# atari-2600-video-mod-v1_0.net
KiCad netlist of a schematic drawn in EAGLE
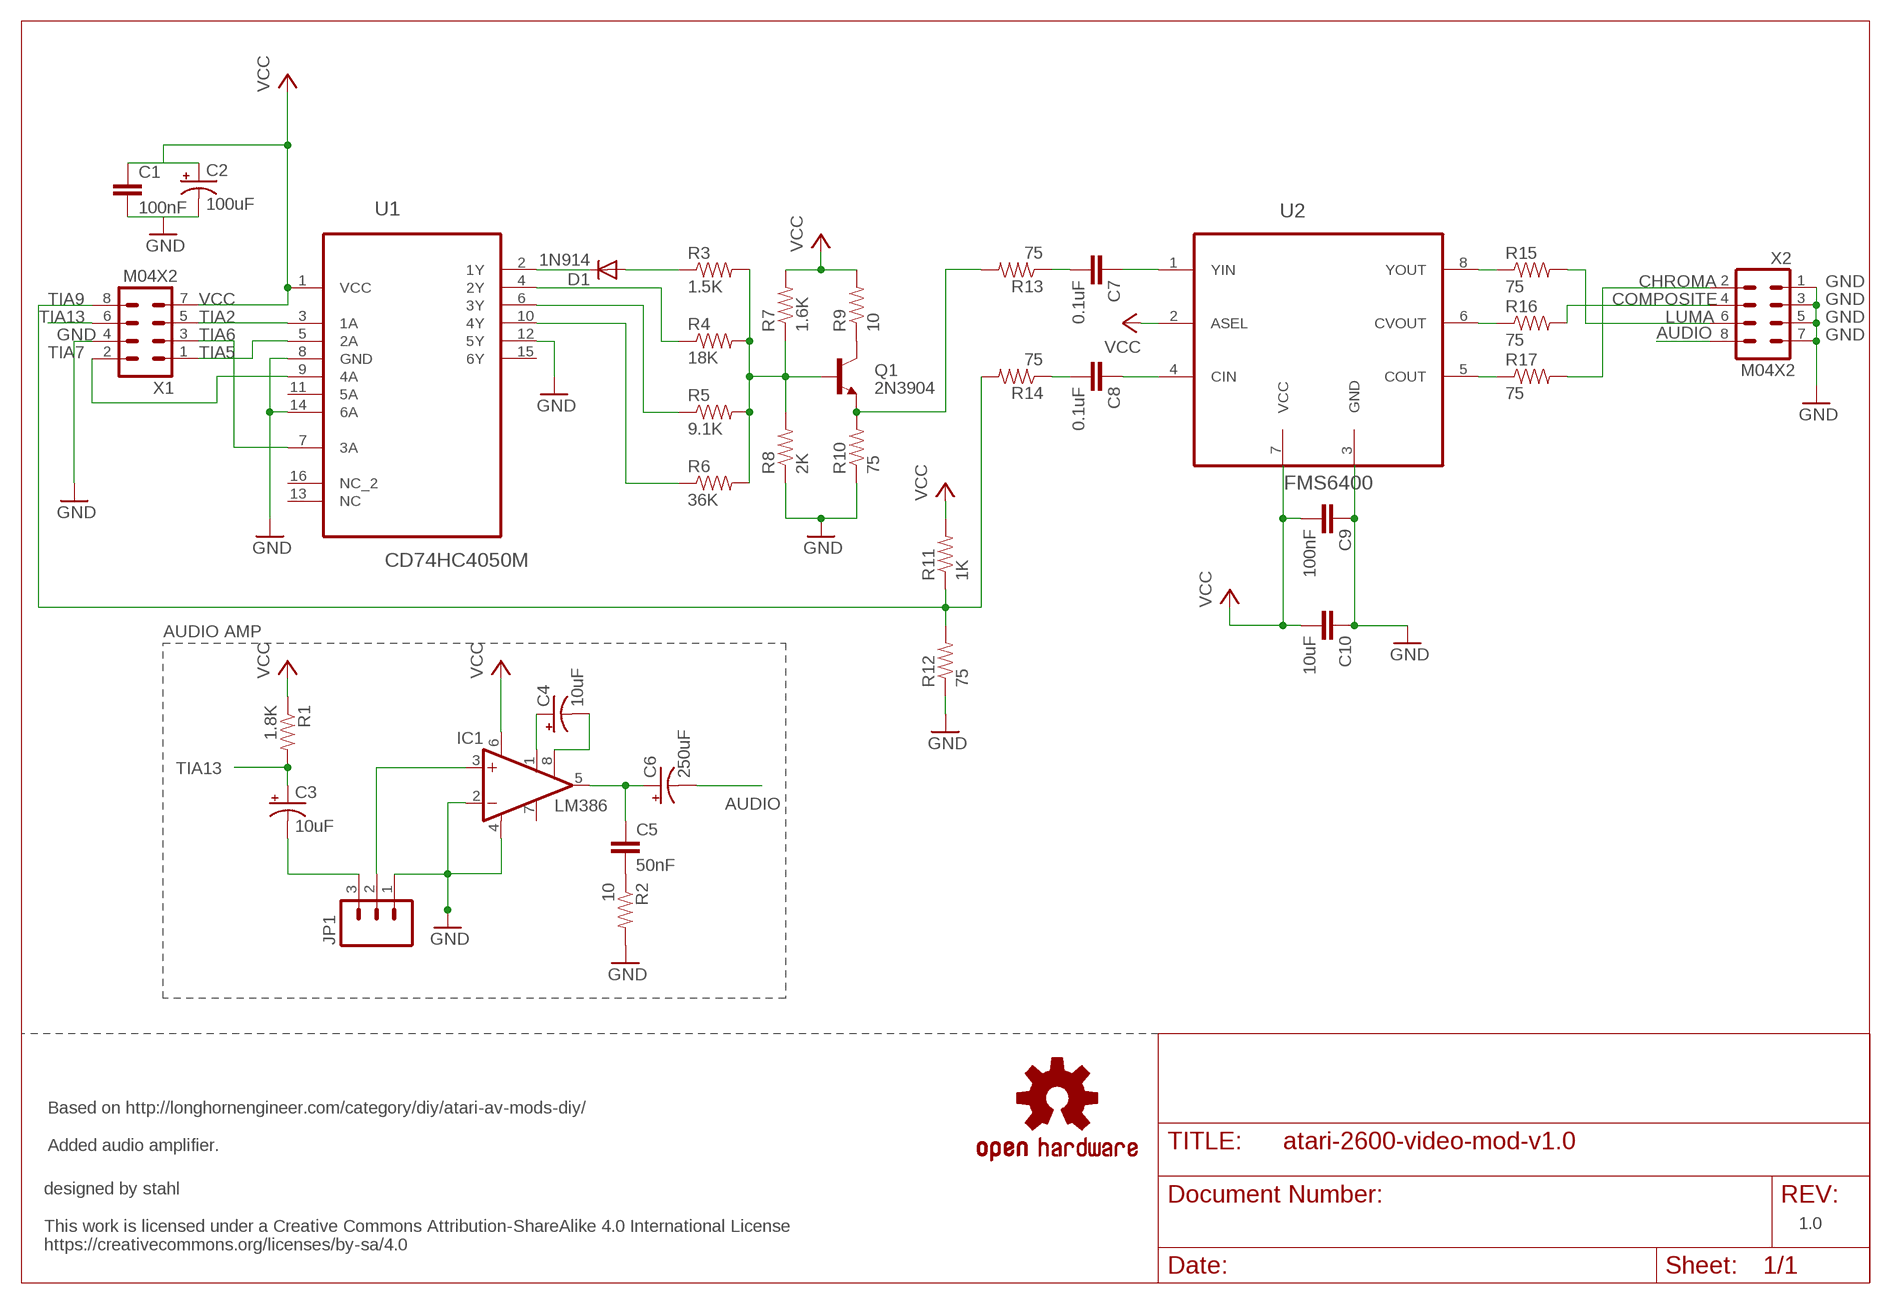
[diagram p0: schematic, sheet 1]

(export (version "E")
  (design (tool "Eeschema 10.0.6"))
  (components
    (comp (ref "C1")
      (value "100nF")
      (footprint "eagle-import:1206")
      (libsource (lib "eagle-import") (part "CAP1206"))
    )
    (comp (ref "C2")
      (value "100uF")
      (footprint "eagle-import:PANASONIC_D")
      (libsource (lib "eagle-import") (part "CPOL-USD"))
    )
    (comp (ref "C3")
      (value "10uF")
      (footprint "eagle-import:PANASONIC_B")
      (libsource (lib "eagle-import") (part "CPOL-USB"))
    )
    (comp (ref "C4")
      (value "10uF")
      (footprint "eagle-import:PANASONIC_B")
      (libsource (lib "eagle-import") (part "CPOL-USB"))
    )
    (comp (ref "C5")
      (value "50nF")
      (footprint "eagle-import:1206")
      (libsource (lib "eagle-import") (part "CAP1206"))
    )
    (comp (ref "C6")
      (value "250uF")
      (footprint "eagle-import:PANASONIC_D")
      (libsource (lib "eagle-import") (part "CPOL-USD"))
    )
    (comp (ref "C7")
      (value "0.1uF")
      (footprint "eagle-import:1206")
      (libsource (lib "eagle-import") (part "CAP1206"))
    )
    (comp (ref "C8")
      (value "0.1uF")
      (footprint "eagle-import:1206")
      (libsource (lib "eagle-import") (part "CAP1206"))
    )
    (comp (ref "C9")
      (value "100nF")
      (footprint "eagle-import:1206")
      (libsource (lib "eagle-import") (part "CAP1206"))
    )
    (comp (ref "C10")
      (value "10uF")
      (footprint "eagle-import:1206")
      (libsource (lib "eagle-import") (part "CAP1206"))
    )
    (comp (ref "D1")
      (value "1N914")
      (footprint "eagle-import:SOD80C")
      (libsource (lib "eagle-import") (part "DIODE-SOD80C"))
    )
    (comp (ref "IC1")
      (value "LM386")
      (footprint "eagle-import:SO08")
      (libsource (lib "eagle-import") (part "LM386?-M1"))
    )
    (comp (ref "JP1")
      (value "M03LONGPADS")
      (footprint "eagle-import:1X03_LONGPADS")
      (libsource (lib "eagle-import") (part "M03LONGPADS"))
    )
    (comp (ref "LOGO1")
      (value "OSHW-LOGOS")
      (footprint "eagle-import:OSHW-LOGO-S")
      (libsource (lib "eagle-import") (part "OSHW-LOGOS"))
    )
    (comp (ref "Q1")
      (value "2N3904")
      (footprint "eagle-import:SOT23")
      (libsource (lib "eagle-import") (part "TRANSISTOR_NPNSOT23"))
    )
    (comp (ref "R1")
      (value "1.8K")
      (footprint "eagle-import:1206")
      (libsource (lib "eagle-import") (part "RESISTOR1206"))
    )
    (comp (ref "R2")
      (value "10")
      (footprint "eagle-import:1206")
      (libsource (lib "eagle-import") (part "RESISTOR1206"))
    )
    (comp (ref "R3")
      (value "1.5K")
      (footprint "eagle-import:1206")
      (libsource (lib "eagle-import") (part "RESISTOR1206"))
    )
    (comp (ref "R4")
      (value "18K")
      (footprint "eagle-import:1206")
      (libsource (lib "eagle-import") (part "RESISTOR1206"))
    )
    (comp (ref "R5")
      (value "9.1K")
      (footprint "eagle-import:1206")
      (libsource (lib "eagle-import") (part "RESISTOR1206"))
    )
    (comp (ref "R6")
      (value "36K")
      (footprint "eagle-import:1206")
      (libsource (lib "eagle-import") (part "RESISTOR1206"))
    )
    (comp (ref "R7")
      (value "1.6K")
      (footprint "eagle-import:1206")
      (libsource (lib "eagle-import") (part "RESISTOR1206"))
    )
    (comp (ref "R8")
      (value "2K")
      (footprint "eagle-import:1206")
      (libsource (lib "eagle-import") (part "RESISTOR1206"))
    )
    (comp (ref "R9")
      (value "10")
      (footprint "eagle-import:1206")
      (libsource (lib "eagle-import") (part "RESISTOR1206"))
    )
    (comp (ref "R10")
      (value "75")
      (footprint "eagle-import:1206")
      (libsource (lib "eagle-import") (part "RESISTOR1206"))
    )
    (comp (ref "R11")
      (value "1K")
      (footprint "eagle-import:1206")
      (libsource (lib "eagle-import") (part "RESISTOR1206"))
    )
    (comp (ref "R12")
      (value "75")
      (footprint "eagle-import:1206")
      (libsource (lib "eagle-import") (part "RESISTOR1206"))
    )
    (comp (ref "R13")
      (value "75")
      (footprint "eagle-import:1206")
      (libsource (lib "eagle-import") (part "RESISTOR1206"))
    )
    (comp (ref "R14")
      (value "75")
      (footprint "eagle-import:1206")
      (libsource (lib "eagle-import") (part "RESISTOR1206"))
    )
    (comp (ref "R15")
      (value "75")
      (footprint "eagle-import:1206")
      (libsource (lib "eagle-import") (part "RESISTOR1206"))
    )
    (comp (ref "R16")
      (value "75")
      (footprint "eagle-import:1206")
      (libsource (lib "eagle-import") (part "RESISTOR1206"))
    )
    (comp (ref "R17")
      (value "75")
      (footprint "eagle-import:1206")
      (libsource (lib "eagle-import") (part "RESISTOR1206"))
    )
    (comp (ref "U1")
      (value "CD74HC4050M")
      (footprint "eagle-import:SOIC127P600X175-16N")
      (libsource (lib "eagle-import") (part "CD74HC4050M"))
    )
    (comp (ref "U2")
      (value "FMS6400")
      (footprint "eagle-import:SOIC-8")
      (libsource (lib "eagle-import") (part "FMS6400"))
    )
    (comp (ref "X1")
      (value "M04X2")
      (footprint "eagle-import:2X4")
      (libsource (lib "eagle-import") (part "M04X2"))
    )
    (comp (ref "X2")
      (value "M04X2")
      (footprint "eagle-import:2X4")
      (libsource (lib "eagle-import") (part "M04X2"))
    )
  )
  (nets
    (net (code "1") (name "/AUDIO") (class "Default")
      (node (ref "C6") (pin "-") (pinfunction "-_-") (pintype "passive"))
      (node (ref "X2") (pin "8") (pinfunction "8_8") (pintype "passive"))
    )
    (net (code "2") (name "/CHROMA") (class "Default")
      (node (ref "R17") (pin "2") (pinfunction "2_2") (pintype "passive"))
      (node (ref "X2") (pin "2") (pinfunction "2_2") (pintype "passive"))
    )
    (net (code "3") (name "/COMPOSITE") (class "Default")
      (node (ref "R16") (pin "2") (pinfunction "2_2") (pintype "passive"))
      (node (ref "X2") (pin "4") (pinfunction "4_4") (pintype "passive"))
    )
    (net (code "4") (name "/LUMA") (class "Default")
      (node (ref "R15") (pin "2") (pinfunction "2_2") (pintype "passive"))
      (node (ref "X2") (pin "6") (pinfunction "6_6") (pintype "passive"))
    )
    (net (code "5") (name "/TIA2") (class "Default")
      (node (ref "U1") (pin "3") (pinfunction "1A_3") (pintype "input"))
      (node (ref "X1") (pin "5") (pinfunction "5_5") (pintype "passive"))
    )
    (net (code "6") (name "/TIA5") (class "Default")
      (node (ref "U1") (pin "5") (pinfunction "2A_5") (pintype "input"))
      (node (ref "X1") (pin "1") (pinfunction "1_1") (pintype "passive"))
    )
    (net (code "7") (name "/TIA6") (class "Default")
      (node (ref "U1") (pin "7") (pinfunction "3A_7") (pintype "input"))
      (node (ref "X1") (pin "3") (pinfunction "3_3") (pintype "passive"))
    )
    (net (code "8") (name "/TIA7") (class "Default")
      (node (ref "U1") (pin "9") (pinfunction "4A_9") (pintype "input"))
      (node (ref "X1") (pin "2") (pinfunction "2_2") (pintype "passive"))
    )
    (net (code "9") (name "/TIA9") (class "Default")
      (node (ref "R11") (pin "1") (pinfunction "1_1") (pintype "passive"))
      (node (ref "R12") (pin "2") (pinfunction "2_2") (pintype "passive"))
      (node (ref "R14") (pin "2") (pinfunction "2_2") (pintype "passive"))
      (node (ref "X1") (pin "8") (pinfunction "8_8") (pintype "passive"))
    )
    (net (code "10") (name "/TIA13") (class "Default")
      (node (ref "C3") (pin "+") (pinfunction "+_+") (pintype "passive"))
      (node (ref "R1") (pin "2") (pinfunction "2_2") (pintype "passive"))
      (node (ref "X1") (pin "6") (pinfunction "6_6") (pintype "passive"))
    )
    (net (code "11") (name "GND") (class "Default")
      (node (ref "C1") (pin "2") (pinfunction "2_2") (pintype "passive"))
      (node (ref "C10") (pin "1") (pinfunction "1_1") (pintype "passive"))
      (node (ref "C2") (pin "-") (pinfunction "-_-") (pintype "passive"))
      (node (ref "C9") (pin "1") (pinfunction "1_1") (pintype "passive"))
      (node (ref "IC1") (pin "2") (pinfunction "-IN_2") (pintype "input"))
      (node (ref "IC1") (pin "4") (pinfunction "GND_4") (pintype "power_in"))
      (node (ref "JP1") (pin "1") (pinfunction "1_1") (pintype "passive"))
      (node (ref "R10") (pin "1") (pinfunction "1_1") (pintype "passive"))
      (node (ref "R12") (pin "1") (pinfunction "1_1") (pintype "passive"))
      (node (ref "R2") (pin "2") (pinfunction "2_2") (pintype "passive"))
      (node (ref "R8") (pin "1") (pinfunction "1_1") (pintype "passive"))
      (node (ref "U1") (pin "12") (pinfunction "5Y_12") (pintype "output"))
      (node (ref "U1") (pin "14") (pinfunction "6A_14") (pintype "input"))
      (node (ref "U1") (pin "8") (pinfunction "GND_8") (pintype "passive"))
      (node (ref "U2") (pin "3") (pinfunction "GND_3") (pintype "passive"))
      (node (ref "X1") (pin "4") (pinfunction "4_4") (pintype "passive"))
      (node (ref "X2") (pin "1") (pinfunction "1_1") (pintype "passive"))
      (node (ref "X2") (pin "3") (pinfunction "3_3") (pintype "passive"))
      (node (ref "X2") (pin "5") (pinfunction "5_5") (pintype "passive"))
      (node (ref "X2") (pin "7") (pinfunction "7_7") (pintype "passive"))
    )
    (net (code "12") (name "Net-(C3-Pad-)") (class "Default")
      (node (ref "C3") (pin "-") (pinfunction "-_-") (pintype "passive"))
      (node (ref "JP1") (pin "3") (pinfunction "3_3") (pintype "passive"))
    )
    (net (code "13") (name "Net-(C4-Pad+)") (class "Default")
      (node (ref "C4") (pin "+") (pinfunction "+_+") (pintype "passive"))
      (node (ref "IC1") (pin "1") (pinfunction "GAIN_1") (pintype "passive"))
    )
    (net (code "14") (name "Net-(C4-Pad-)") (class "Default")
      (node (ref "C4") (pin "-") (pinfunction "-_-") (pintype "passive"))
      (node (ref "IC1") (pin "8") (pinfunction "GAIN_8") (pintype "passive"))
    )
    (net (code "15") (name "Net-(C5-Pad2)") (class "Default")
      (node (ref "C5") (pin "2") (pinfunction "2_2") (pintype "passive"))
      (node (ref "R2") (pin "1") (pinfunction "1_1") (pintype "passive"))
    )
    (net (code "16") (name "Net-(C7-Pad2)") (class "Default")
      (node (ref "C7") (pin "2") (pinfunction "2_2") (pintype "passive"))
      (node (ref "R13") (pin "1") (pinfunction "1_1") (pintype "passive"))
    )
    (net (code "17") (name "Net-(C8-Pad2)") (class "Default")
      (node (ref "C8") (pin "2") (pinfunction "2_2") (pintype "passive"))
      (node (ref "R14") (pin "1") (pinfunction "1_1") (pintype "passive"))
    )
    (net (code "18") (name "Net-(D1-PadA)") (class "Default")
      (node (ref "D1") (pin "A") (pinfunction "A_A") (pintype "passive"))
      (node (ref "R3") (pin "1") (pinfunction "1_1") (pintype "passive"))
    )
    (net (code "19") (name "Net-(IC1-+IN)") (class "Default")
      (node (ref "IC1") (pin "3") (pinfunction "+IN_3") (pintype "input"))
      (node (ref "JP1") (pin "2") (pinfunction "2_2") (pintype "passive"))
    )
    (net (code "20") (name "Net-(IC1-OUT)") (class "Default")
      (node (ref "C5") (pin "1") (pinfunction "1_1") (pintype "passive"))
      (node (ref "C6") (pin "+") (pinfunction "+_+") (pintype "passive"))
      (node (ref "IC1") (pin "5") (pinfunction "OUT_5") (pintype "output"))
    )
    (net (code "21") (name "Net-(Q1-B)") (class "Default")
      (node (ref "Q1") (pin "1") (pinfunction "B_1") (pintype "passive"))
      (node (ref "R3") (pin "2") (pinfunction "2_2") (pintype "passive"))
      (node (ref "R4") (pin "2") (pinfunction "2_2") (pintype "passive"))
      (node (ref "R5") (pin "2") (pinfunction "2_2") (pintype "passive"))
      (node (ref "R6") (pin "2") (pinfunction "2_2") (pintype "passive"))
      (node (ref "R7") (pin "1") (pinfunction "1_1") (pintype "passive"))
      (node (ref "R8") (pin "2") (pinfunction "2_2") (pintype "passive"))
    )
    (net (code "22") (name "Net-(Q1-C)") (class "Default")
      (node (ref "Q1") (pin "3") (pinfunction "C_3") (pintype "passive"))
      (node (ref "R9") (pin "1") (pinfunction "1_1") (pintype "passive"))
    )
    (net (code "23") (name "Net-(Q1-E)") (class "Default")
      (node (ref "Q1") (pin "2") (pinfunction "E_2") (pintype "passive"))
      (node (ref "R10") (pin "2") (pinfunction "2_2") (pintype "passive"))
      (node (ref "R13") (pin "2") (pinfunction "2_2") (pintype "passive"))
    )
    (net (code "24") (name "Net-(U1-1Y)") (class "Default")
      (node (ref "D1") (pin "C") (pinfunction "C_C") (pintype "passive"))
      (node (ref "U1") (pin "2") (pinfunction "1Y_2") (pintype "output"))
    )
    (net (code "25") (name "Net-(U1-2Y)") (class "Default")
      (node (ref "R4") (pin "1") (pinfunction "1_1") (pintype "passive"))
      (node (ref "U1") (pin "4") (pinfunction "2Y_4") (pintype "output"))
    )
    (net (code "26") (name "Net-(U1-3Y)") (class "Default")
      (node (ref "R5") (pin "1") (pinfunction "1_1") (pintype "passive"))
      (node (ref "U1") (pin "6") (pinfunction "3Y_6") (pintype "output"))
    )
    (net (code "27") (name "Net-(U1-4Y)") (class "Default")
      (node (ref "R6") (pin "1") (pinfunction "1_1") (pintype "passive"))
      (node (ref "U1") (pin "10") (pinfunction "4Y_10") (pintype "output"))
    )
    (net (code "28") (name "Net-(U2-CIN)") (class "Default")
      (node (ref "C8") (pin "1") (pinfunction "1_1") (pintype "passive"))
      (node (ref "U2") (pin "4") (pinfunction "CIN_4") (pintype "input"))
    )
    (net (code "29") (name "Net-(U2-COUT)") (class "Default")
      (node (ref "R17") (pin "1") (pinfunction "1_1") (pintype "passive"))
      (node (ref "U2") (pin "5") (pinfunction "COUT_5") (pintype "input"))
    )
    (net (code "30") (name "Net-(U2-CVOUT)") (class "Default")
      (node (ref "R16") (pin "1") (pinfunction "1_1") (pintype "passive"))
      (node (ref "U2") (pin "6") (pinfunction "CVOUT_6") (pintype "output"))
    )
    (net (code "31") (name "Net-(U2-YIN)") (class "Default")
      (node (ref "C7") (pin "1") (pinfunction "1_1") (pintype "passive"))
      (node (ref "U2") (pin "1") (pinfunction "YIN_1") (pintype "input"))
    )
    (net (code "32") (name "Net-(U2-YOUT)") (class "Default")
      (node (ref "R15") (pin "1") (pinfunction "1_1") (pintype "passive"))
      (node (ref "U2") (pin "8") (pinfunction "YOUT_8") (pintype "output"))
    )
    (net (code "33") (name "VCC") (class "Default")
      (node (ref "C1") (pin "1") (pinfunction "1_1") (pintype "passive"))
      (node (ref "C10") (pin "2") (pinfunction "2_2") (pintype "passive"))
      (node (ref "C2") (pin "+") (pinfunction "+_+") (pintype "passive"))
      (node (ref "C9") (pin "2") (pinfunction "2_2") (pintype "passive"))
      (node (ref "IC1") (pin "6") (pinfunction "VS_6") (pintype "power_in"))
      (node (ref "R1") (pin "1") (pinfunction "1_1") (pintype "passive"))
      (node (ref "R11") (pin "2") (pinfunction "2_2") (pintype "passive"))
      (node (ref "R7") (pin "2") (pinfunction "2_2") (pintype "passive"))
      (node (ref "R9") (pin "2") (pinfunction "2_2") (pintype "passive"))
      (node (ref "U1") (pin "1") (pinfunction "VCC_1") (pintype "power_in"))
      (node (ref "U2") (pin "2") (pinfunction "ASEL_2") (pintype "input"))
      (node (ref "U2") (pin "7") (pinfunction "VCC_7") (pintype "power_in"))
      (node (ref "X1") (pin "7") (pinfunction "7_7") (pintype "passive"))
    )
    (net (code "34") (name "unconnected-(IC1-BYPASS-Pad7)") (class "Default")
      (node (ref "IC1") (pin "7") (pinfunction "BYPASS_7") (pintype "passive"))
    )
    (net (code "35") (name "unconnected-(U1-5A-Pad11)") (class "Default")
      (node (ref "U1") (pin "11") (pinfunction "5A_11") (pintype "input"))
    )
    (net (code "36") (name "unconnected-(U1-6Y-Pad15)") (class "Default")
      (node (ref "U1") (pin "15") (pinfunction "6Y_15") (pintype "output"))
    )
    (net (code "37") (name "unconnected-(U1-NC-Pad13)") (class "Default")
      (node (ref "U1") (pin "13") (pinfunction "NC_13") (pintype "no_connect"))
    )
    (net (code "38") (name "unconnected-(U1-NC_2-Pad16)") (class "Default")
      (node (ref "U1") (pin "16") (pinfunction "NC_2_16") (pintype "no_connect"))
    )
  )
)
